# Main.net
KiCad netlist of a schematic drawn in EAGLE
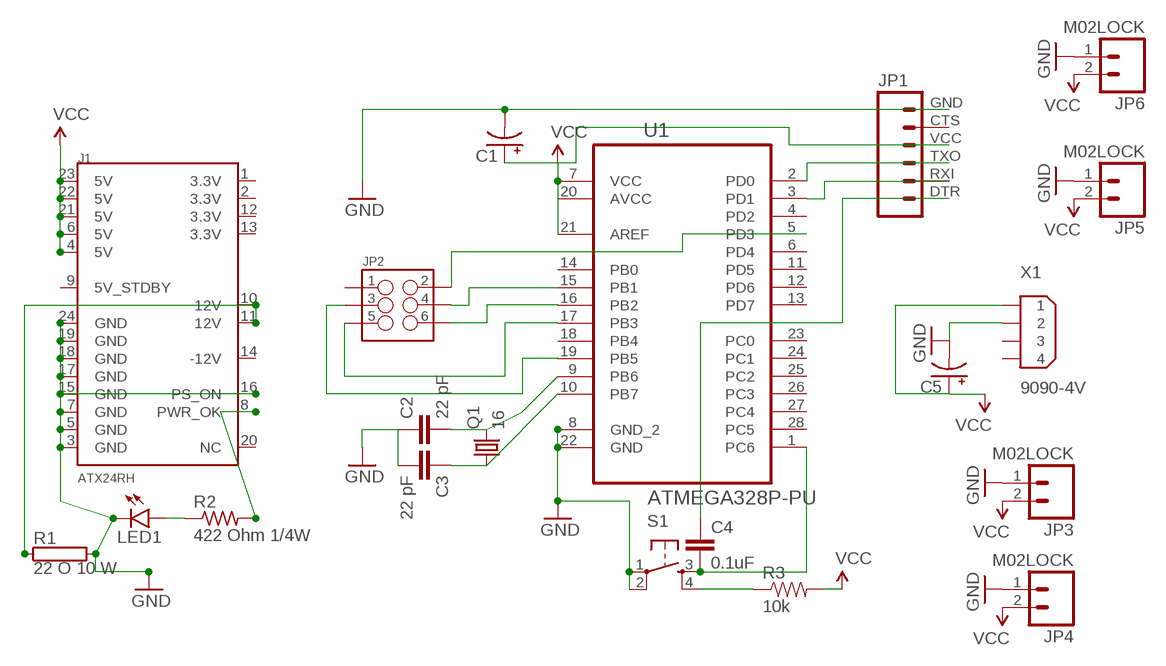
[diagram p0: schematic, sheet 1]

(export (version "E")
  (design (tool "Eeschema 10.0.6"))
  (components
    (comp (ref "C1")
      (value "CAP_POLPTH2")
      (footprint "eagle-import:CPOL-RADIAL-10UF-25V")
      (libsource (lib "eagle-import") (part "CAP_POLPTH2"))
    )
    (comp (ref "C2")
      (value "22 pF")
      (footprint "eagle-import:C2.5-3")
      (libsource (lib "eagle-import") (part "C2,5-3"))
    )
    (comp (ref "C3")
      (value "22 pF")
      (footprint "eagle-import:C2.5-3")
      (libsource (lib "eagle-import") (part "C2,5-3"))
    )
    (comp (ref "C4")
      (value "0.1uF")
      (footprint "eagle-import:0603-CAP")
      (libsource (lib "eagle-import") (part "0.1UF-25V-5%(0603)"))
    )
    (comp (ref "C5")
      (value "CAP_POLPTH2")
      (footprint "eagle-import:CPOL-RADIAL-10UF-25V")
      (libsource (lib "eagle-import") (part "CAP_POLPTH2"))
    )
    (comp (ref "J1")
      (value "ATX24RH")
      (footprint "eagle-import:ATX24_RIGHT_ANGLE")
      (libsource (lib "eagle-import") (part "ATX24RH"))
    )
    (comp (ref "JP1")
      (value "M06SIP")
      (footprint "eagle-import:1X06")
      (libsource (lib "eagle-import") (part "M06SIP"))
    )
    (comp (ref "JP2")
      (value "M03X22X3_SILK_SM")
      (footprint "eagle-import:2X3")
      (libsource (lib "eagle-import") (part "M03X22X3_SILK_SM"))
    )
    (comp (ref "JP3")
      (value "M02LOCK")
      (footprint "eagle-import:1X02_LOCK")
      (libsource (lib "eagle-import") (part "M02LOCK"))
    )
    (comp (ref "JP4")
      (value "M02LOCK")
      (footprint "eagle-import:1X02_LOCK")
      (libsource (lib "eagle-import") (part "M02LOCK"))
    )
    (comp (ref "JP5")
      (value "M02LOCK")
      (footprint "eagle-import:1X02_LOCK")
      (libsource (lib "eagle-import") (part "M02LOCK"))
    )
    (comp (ref "JP6")
      (value "M02LOCK")
      (footprint "eagle-import:1X02_LOCK")
      (libsource (lib "eagle-import") (part "M02LOCK"))
    )
    (comp (ref "LED1")
      (value "LED0603")
      (footprint "eagle-import:LED-0603")
      (libsource (lib "eagle-import") (part "LED0603"))
    )
    (comp (ref "Q1")
      (value "16")
      (footprint "eagle-import:HC49_S")
      (libsource (lib "eagle-import") (part "CRYSTALHC49S"))
    )
    (comp (ref "R1")
      (value "22 O 10 W")
      (footprint "eagle-import:RWM8X45")
      (libsource (lib "eagle-import") (part "RRWM8X45"))
    )
    (comp (ref "R2")
      (value "422 Ohm 1/4W")
      (footprint "eagle-import:M3216")
      (libsource (lib "eagle-import") (part "R-US_M3216"))
    )
    (comp (ref "R3")
      (value "10k")
      (footprint "eagle-import:AXIAL-0.3")
      (libsource (lib "eagle-import") (part "10KOHM-1/4W5%(PTH)"))
    )
    (comp (ref "S1")
      (value "TAC_SWITCHPTH")
      (footprint "eagle-import:TACTILE-PTH")
      (libsource (lib "eagle-import") (part "TAC_SWITCHPTH"))
    )
    (comp (ref "U1")
      (value "ATMEGA328P-PU")
      (footprint "eagle-import:DIP254P762X457-28")
      (libsource (lib "eagle-import") (part "ATMEGA328P-PU"))
    )
    (comp (ref "X1")
      (value "9090-4V")
      (footprint "eagle-import:9090-4V")
      (libsource (lib "eagle-import") (part "9090-4V"))
    )
  )
  (nets
    (net (code "1") (name "GND") (class "Default")
      (node (ref "C1") (pin "2") (pinfunction "-_2") (pintype "passive"))
      (node (ref "C2") (pin "1") (pinfunction "1_1") (pintype "passive"))
      (node (ref "C3") (pin "2") (pinfunction "2_2") (pintype "passive"))
      (node (ref "C5") (pin "2") (pinfunction "-_2") (pintype "passive"))
      (node (ref "J1") (pin "15") (pinfunction "GND_15") (pintype "bidirectional"))
      (node (ref "J1") (pin "16") (pinfunction "PS_ON_16") (pintype "bidirectional"))
      (node (ref "J1") (pin "17") (pinfunction "GND_17") (pintype "bidirectional"))
      (node (ref "J1") (pin "18") (pinfunction "GND_18") (pintype "bidirectional"))
      (node (ref "J1") (pin "19") (pinfunction "GND_19") (pintype "bidirectional"))
      (node (ref "J1") (pin "24") (pinfunction "GND_24") (pintype "bidirectional"))
      (node (ref "J1") (pin "3") (pinfunction "GND_3") (pintype "bidirectional"))
      (node (ref "J1") (pin "5") (pinfunction "GND_5") (pintype "bidirectional"))
      (node (ref "J1") (pin "7") (pinfunction "GND_7") (pintype "bidirectional"))
      (node (ref "JP1") (pin "GND") (pinfunction "6_GND") (pintype "passive"))
      (node (ref "JP3") (pin "1") (pinfunction "1_1") (pintype "passive"))
      (node (ref "JP4") (pin "1") (pinfunction "1_1") (pintype "passive"))
      (node (ref "JP5") (pin "1") (pinfunction "1_1") (pintype "passive"))
      (node (ref "JP6") (pin "1") (pinfunction "1_1") (pintype "passive"))
      (node (ref "LED1") (pin "C") (pinfunction "C_C") (pintype "passive"))
      (node (ref "R1") (pin "2") (pinfunction "2_2") (pintype "passive"))
      (node (ref "S1") (pin "1") (pinfunction "1_1") (pintype "passive"))
      (node (ref "S1") (pin "2") (pinfunction "2_2") (pintype "passive"))
      (node (ref "U1") (pin "22") (pinfunction "GND_22") (pintype "passive"))
      (node (ref "U1") (pin "8") (pinfunction "GND_2_8") (pintype "passive"))
      (node (ref "X1") (pin "2") (pinfunction "2_2") (pintype "passive"))
    )
    (net (code "2") (name "Net-(J1-12V-Pad10)") (class "Default")
      (node (ref "J1") (pin "10") (pinfunction "12V_10") (pintype "bidirectional"))
      (node (ref "J1") (pin "11") (pinfunction "12V_11") (pintype "bidirectional"))
      (node (ref "R1") (pin "1") (pinfunction "1_1") (pintype "passive"))
    )
    (net (code "3") (name "Net-(J1-PWR_OK)") (class "Default")
      (node (ref "J1") (pin "8") (pinfunction "PWR_OK_8") (pintype "bidirectional"))
      (node (ref "R2") (pin "2") (pinfunction "2_2") (pintype "passive"))
    )
    (net (code "4") (name "Net-(JP1-1)") (class "Default")
      (node (ref "C4") (pin "1") (pinfunction "1_1") (pintype "passive"))
      (node (ref "JP1") (pin "DTR") (pinfunction "1_DTR") (pintype "passive"))
    )
    (net (code "5") (name "Net-(JP1-2)") (class "Default")
      (node (ref "JP1") (pin "RXI") (pinfunction "2_RXI") (pintype "passive"))
      (node (ref "U1") (pin "3") (pinfunction "PD1_3") (pintype "bidirectional"))
    )
    (net (code "6") (name "Net-(JP1-3)") (class "Default")
      (node (ref "JP1") (pin "TXO") (pinfunction "3_TXO") (pintype "passive"))
      (node (ref "U1") (pin "2") (pinfunction "PD0_2") (pintype "bidirectional"))
    )
    (net (code "7") (name "Net-(LED1-PadA)") (class "Default")
      (node (ref "LED1") (pin "A") (pinfunction "A_A") (pintype "passive"))
      (node (ref "R2") (pin "1") (pinfunction "1_1") (pintype "passive"))
    )
    (net (code "8") (name "Net-(R3-1)") (class "Default")
      (node (ref "R3") (pin "P$1") (pinfunction "1_P$1") (pintype "passive"))
      (node (ref "S1") (pin "4") (pinfunction "4_4") (pintype "passive"))
    )
    (net (code "9") (name "Net-(U1-PB1)") (class "Default")
      (node (ref "JP2") (pin "4") (pinfunction "4_4") (pintype "bidirectional"))
      (node (ref "U1") (pin "15") (pinfunction "PB1_15") (pintype "bidirectional"))
    )
    (net (code "10") (name "Net-(U1-PB2)") (class "Default")
      (node (ref "JP2") (pin "6") (pinfunction "6_6") (pintype "bidirectional"))
      (node (ref "U1") (pin "16") (pinfunction "PB2_16") (pintype "bidirectional"))
    )
    (net (code "11") (name "Net-(U1-PB3)") (class "Default")
      (node (ref "JP2") (pin "5") (pinfunction "5_5") (pintype "bidirectional"))
      (node (ref "U1") (pin "17") (pinfunction "PB3_17") (pintype "bidirectional"))
    )
    (net (code "12") (name "Net-(U1-PB5)") (class "Default")
      (node (ref "JP2") (pin "3") (pinfunction "3_3") (pintype "bidirectional"))
      (node (ref "U1") (pin "19") (pinfunction "PB5_19") (pintype "bidirectional"))
    )
    (net (code "13") (name "Net-(U1-PB6)") (class "Default")
      (node (ref "C2") (pin "2") (pinfunction "2_2") (pintype "passive"))
      (node (ref "Q1") (pin "2") (pinfunction "2_2") (pintype "passive"))
      (node (ref "U1") (pin "9") (pinfunction "PB6_9") (pintype "bidirectional"))
    )
    (net (code "14") (name "Net-(U1-PB7)") (class "Default")
      (node (ref "C3") (pin "1") (pinfunction "1_1") (pintype "passive"))
      (node (ref "Q1") (pin "1") (pinfunction "1_1") (pintype "passive"))
      (node (ref "U1") (pin "10") (pinfunction "PB7_10") (pintype "bidirectional"))
    )
    (net (code "15") (name "Net-(U1-PC6)") (class "Default")
      (node (ref "C4") (pin "2") (pinfunction "2_2") (pintype "passive"))
      (node (ref "S1") (pin "3") (pinfunction "3_3") (pintype "passive"))
      (node (ref "U1") (pin "1") (pinfunction "PC6_1") (pintype "bidirectional"))
    )
    (net (code "16") (name "Net-(U1-PD3)") (class "Default")
      (node (ref "JP2") (pin "2") (pinfunction "2_2") (pintype "bidirectional"))
      (node (ref "U1") (pin "5") (pinfunction "PD3_5") (pintype "bidirectional"))
    )
    (net (code "17") (name "VCC") (class "Default")
      (node (ref "C1") (pin "1") (pinfunction "+_1") (pintype "passive"))
      (node (ref "C5") (pin "1") (pinfunction "+_1") (pintype "passive"))
      (node (ref "J1") (pin "21") (pinfunction "5V_21") (pintype "bidirectional"))
      (node (ref "J1") (pin "22") (pinfunction "5V_22") (pintype "bidirectional"))
      (node (ref "J1") (pin "23") (pinfunction "5V_23") (pintype "bidirectional"))
      (node (ref "J1") (pin "4") (pinfunction "5V_4") (pintype "bidirectional"))
      (node (ref "J1") (pin "6") (pinfunction "5V_6") (pintype "bidirectional"))
      (node (ref "JP1") (pin "VCC") (pinfunction "4_VCC") (pintype "passive"))
      (node (ref "JP3") (pin "2") (pinfunction "2_2") (pintype "passive"))
      (node (ref "JP4") (pin "2") (pinfunction "2_2") (pintype "passive"))
      (node (ref "JP5") (pin "2") (pinfunction "2_2") (pintype "passive"))
      (node (ref "JP6") (pin "2") (pinfunction "2_2") (pintype "passive"))
      (node (ref "R3") (pin "P$2") (pinfunction "2_P$2") (pintype "passive"))
      (node (ref "U1") (pin "20") (pinfunction "AVCC_20") (pintype "power_in"))
      (node (ref "U1") (pin "21") (pinfunction "AREF_21") (pintype "input"))
      (node (ref "U1") (pin "7") (pinfunction "VCC_7") (pintype "power_in"))
      (node (ref "X1") (pin "1") (pinfunction "1_1") (pintype "passive"))
    )
    (net (code "18") (name "unconnected-(J1--12V-Pad14)") (class "Default")
      (node (ref "J1") (pin "14") (pinfunction "-12V_14") (pintype "bidirectional"))
    )
    (net (code "19") (name "unconnected-(J1-3.3V-Pad1)") (class "Default")
      (node (ref "J1") (pin "1") (pinfunction "3.3V_1") (pintype "bidirectional"))
    )
    (net (code "20") (name "unconnected-(J1-3.3V-Pad2)") (class "Default")
      (node (ref "J1") (pin "2") (pinfunction "3.3V_2") (pintype "bidirectional"))
    )
    (net (code "21") (name "unconnected-(J1-3.3V-Pad12)") (class "Default")
      (node (ref "J1") (pin "12") (pinfunction "3.3V_12") (pintype "bidirectional"))
    )
    (net (code "22") (name "unconnected-(J1-3.3V-Pad13)") (class "Default")
      (node (ref "J1") (pin "13") (pinfunction "3.3V_13") (pintype "bidirectional"))
    )
    (net (code "23") (name "unconnected-(J1-5V_STDBY-Pad9)") (class "Default")
      (node (ref "J1") (pin "9") (pinfunction "5V_STDBY_9") (pintype "bidirectional"))
    )
    (net (code "24") (name "unconnected-(J1-NC-Pad20)") (class "Default")
      (node (ref "J1") (pin "20") (pinfunction "NC_20") (pintype "bidirectional"))
    )
    (net (code "25") (name "unconnected-(JP1-5-PadCTS)") (class "Default")
      (node (ref "JP1") (pin "CTS") (pinfunction "5_CTS") (pintype "passive"))
    )
    (net (code "26") (name "unconnected-(JP2-Pad1)") (class "Default")
      (node (ref "JP2") (pin "1") (pinfunction "1_1") (pintype "bidirectional"))
    )
    (net (code "27") (name "unconnected-(U1-PB0-Pad14)") (class "Default")
      (node (ref "U1") (pin "14") (pinfunction "PB0_14") (pintype "bidirectional"))
    )
    (net (code "28") (name "unconnected-(U1-PB4-Pad18)") (class "Default")
      (node (ref "U1") (pin "18") (pinfunction "PB4_18") (pintype "bidirectional"))
    )
    (net (code "29") (name "unconnected-(U1-PC0-Pad23)") (class "Default")
      (node (ref "U1") (pin "23") (pinfunction "PC0_23") (pintype "bidirectional"))
    )
    (net (code "30") (name "unconnected-(U1-PC1-Pad24)") (class "Default")
      (node (ref "U1") (pin "24") (pinfunction "PC1_24") (pintype "bidirectional"))
    )
    (net (code "31") (name "unconnected-(U1-PC2-Pad25)") (class "Default")
      (node (ref "U1") (pin "25") (pinfunction "PC2_25") (pintype "bidirectional"))
    )
    (net (code "32") (name "unconnected-(U1-PC3-Pad26)") (class "Default")
      (node (ref "U1") (pin "26") (pinfunction "PC3_26") (pintype "bidirectional"))
    )
    (net (code "33") (name "unconnected-(U1-PC4-Pad27)") (class "Default")
      (node (ref "U1") (pin "27") (pinfunction "PC4_27") (pintype "bidirectional"))
    )
    (net (code "34") (name "unconnected-(U1-PC5-Pad28)") (class "Default")
      (node (ref "U1") (pin "28") (pinfunction "PC5_28") (pintype "bidirectional"))
    )
    (net (code "35") (name "unconnected-(U1-PD2-Pad4)") (class "Default")
      (node (ref "U1") (pin "4") (pinfunction "PD2_4") (pintype "bidirectional"))
    )
    (net (code "36") (name "unconnected-(U1-PD4-Pad6)") (class "Default")
      (node (ref "U1") (pin "6") (pinfunction "PD4_6") (pintype "bidirectional"))
    )
    (net (code "37") (name "unconnected-(U1-PD5-Pad11)") (class "Default")
      (node (ref "U1") (pin "11") (pinfunction "PD5_11") (pintype "bidirectional"))
    )
    (net (code "38") (name "unconnected-(U1-PD6-Pad12)") (class "Default")
      (node (ref "U1") (pin "12") (pinfunction "PD6_12") (pintype "bidirectional"))
    )
    (net (code "39") (name "unconnected-(U1-PD7-Pad13)") (class "Default")
      (node (ref "U1") (pin "13") (pinfunction "PD7_13") (pintype "bidirectional"))
    )
    (net (code "40") (name "unconnected-(X1-Pad3)") (class "Default")
      (node (ref "X1") (pin "3") (pinfunction "3_3") (pintype "passive"))
    )
    (net (code "41") (name "unconnected-(X1-Pad4)") (class "Default")
      (node (ref "X1") (pin "4") (pinfunction "4_4") (pintype "passive"))
    )
  )
)
